# PlatingBoard.net
KiCad netlist of a schematic drawn in EAGLE
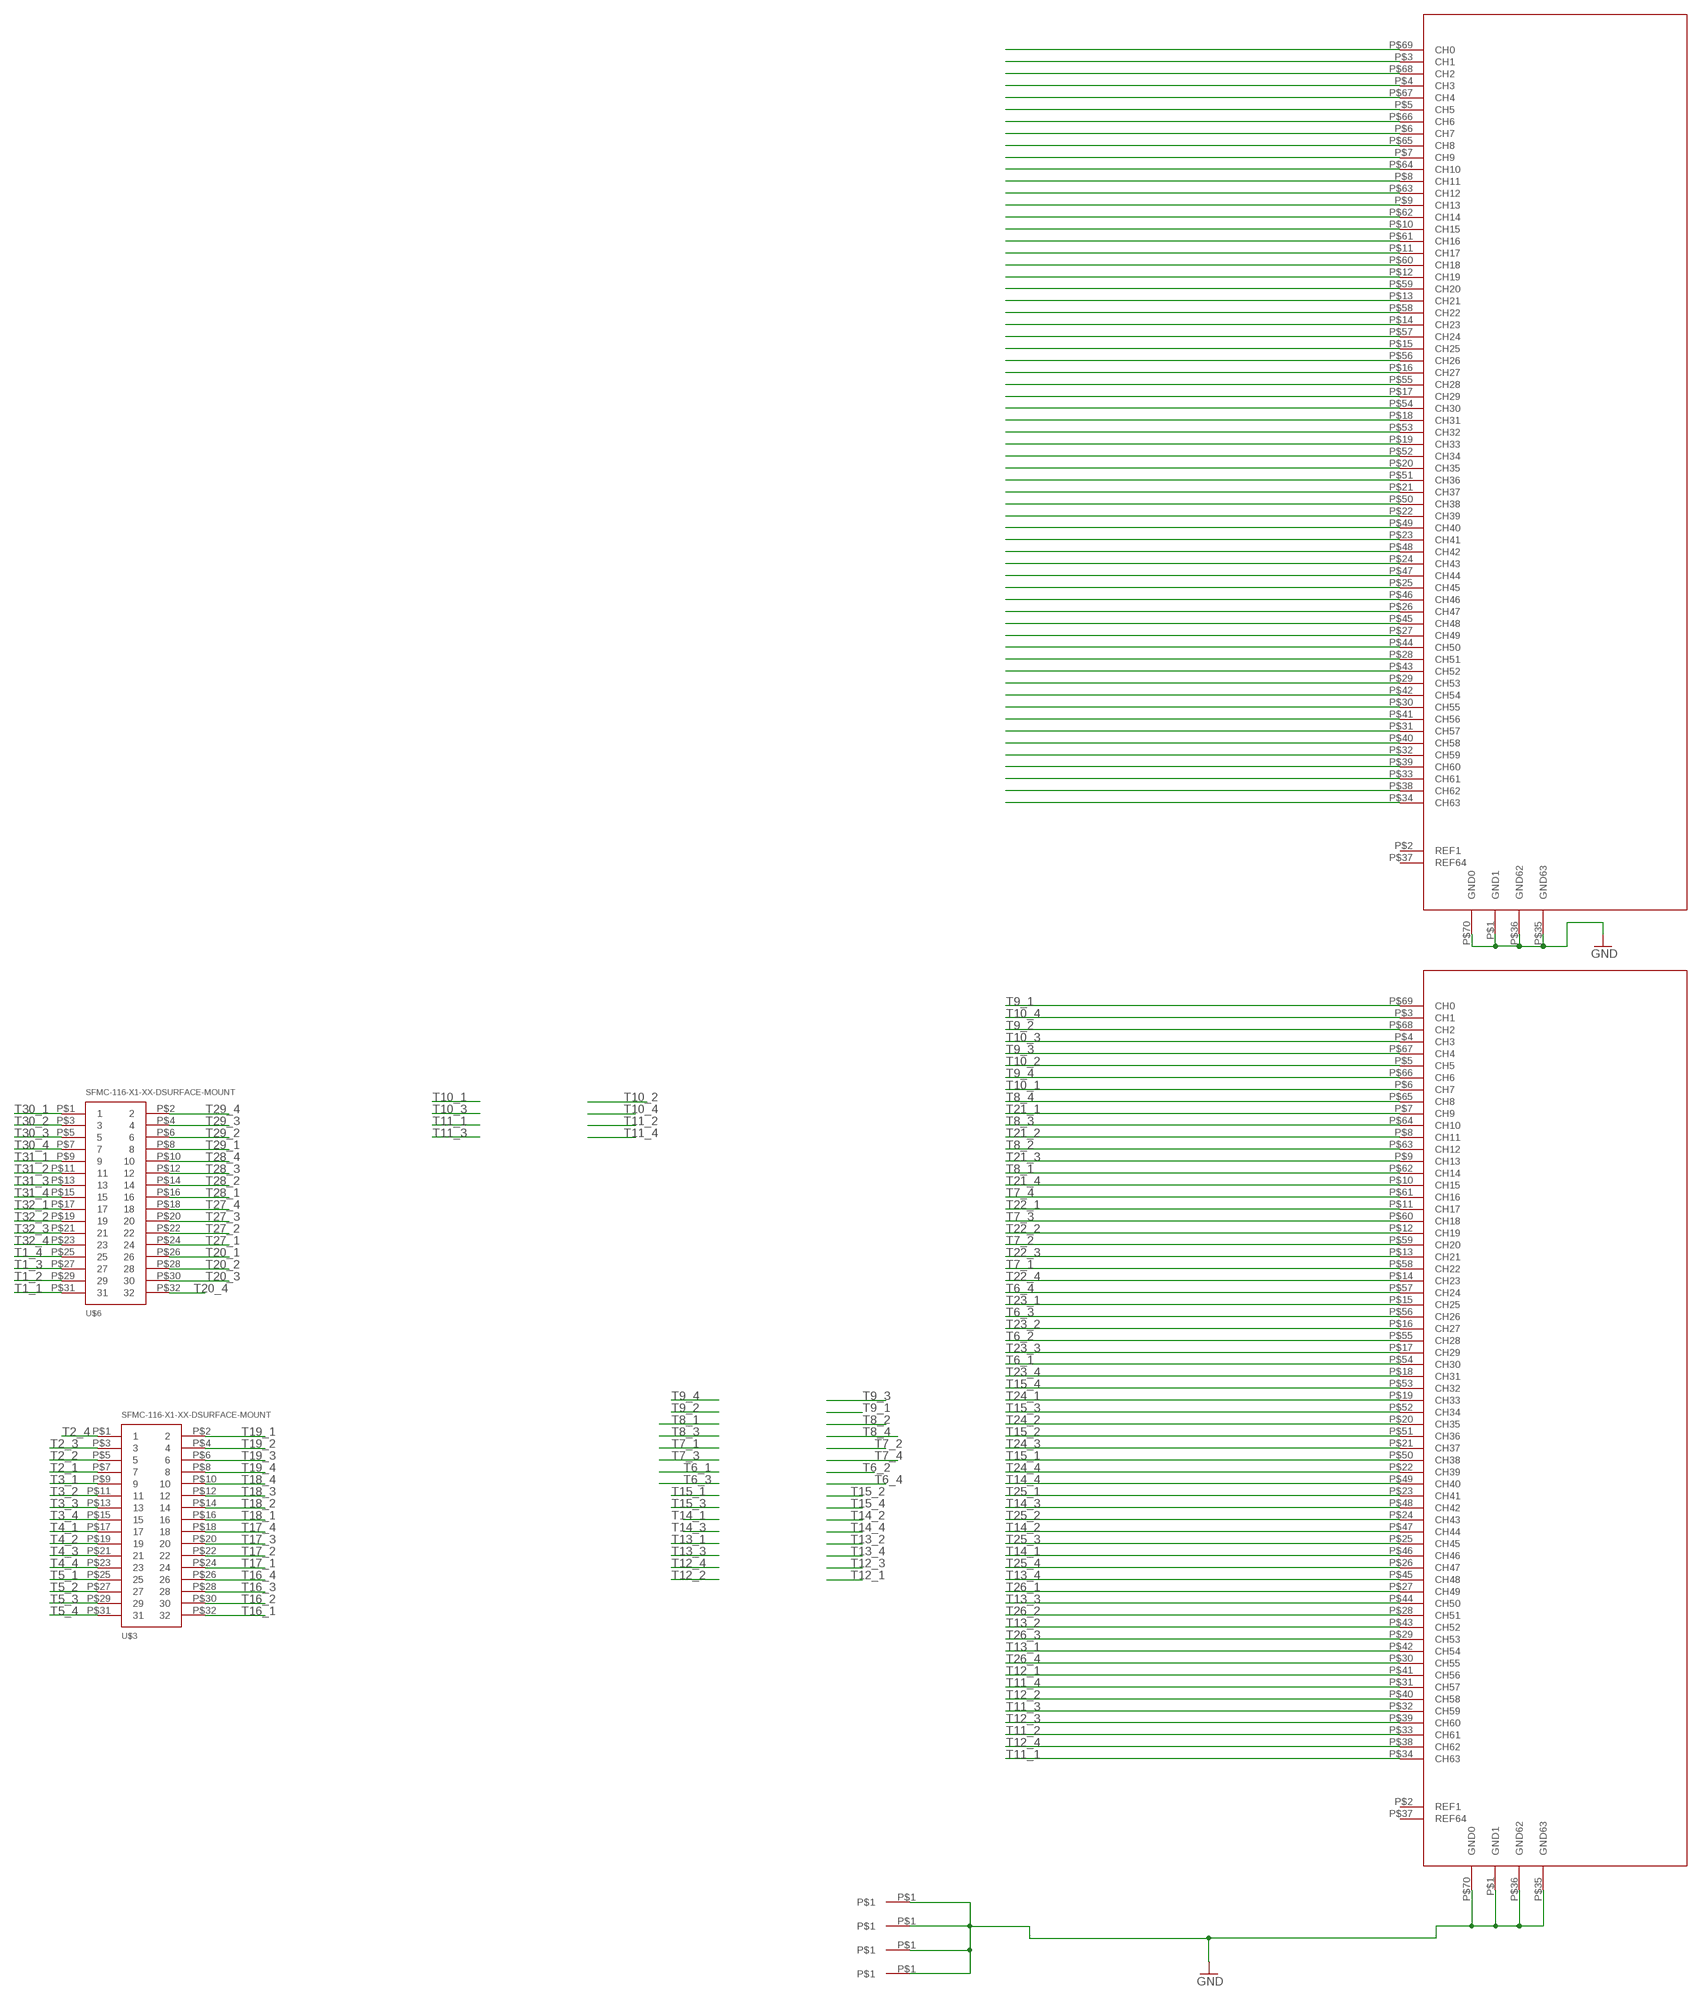
[diagram p0: schematic, sheet 1]

(export (version "E")
  (design (tool "Eeschema 10.0.6"))
  (components
    (comp (ref "U$1")
      (value "TARRAYSHUTTLEHOLE")
      (footprint "eagle-import:TARRAYSHUTTLEHOLE")
      (libsource (lib "eagle-import") (part "TARRAYSHUTTLEHOLE"))
    )
    (comp (ref "U$2")
      (value "TARRAYSHUTTLEHOLE")
      (footprint "eagle-import:TARRAYSHUTTLEHOLE")
      (libsource (lib "eagle-import") (part "TARRAYSHUTTLEHOLE"))
    )
    (comp (ref "U$3")
      (value "SFMC-116-X1-XX-DSURFACE-MOUNT")
      (footprint "eagle-import:SFMC-116-X2-XX-D")
      (libsource (lib "eagle-import") (part "SFMC-116-X1-XX-DSURFACE-MOUNT"))
    )
    (comp (ref "U$4")
      (value "TARRAYSHUTTLEHOLE")
      (footprint "eagle-import:TARRAYSHUTTLEHOLE")
      (libsource (lib "eagle-import") (part "TARRAYSHUTTLEHOLE"))
    )
    (comp (ref "U$5")
      (value "TARRAYSHUTTLEHOLE")
      (footprint "eagle-import:TARRAYSHUTTLEHOLE")
      (libsource (lib "eagle-import") (part "TARRAYSHUTTLEHOLE"))
    )
    (comp (ref "U$6")
      (value "SFMC-116-X1-XX-DSURFACE-MOUNT")
      (footprint "eagle-import:SFMC-116-X2-XX-D")
      (libsource (lib "eagle-import") (part "SFMC-116-X1-XX-DSURFACE-MOUNT"))
    )
    (comp (ref "U$11")
      (value "HIROSE-70PIN-RECEPTACLE")
      (footprint "eagle-import:DF40HC-70DS-0.4V")
      (libsource (lib "eagle-import") (part "HIROSE-70PIN-RECEPTACLE"))
    )
    (comp (ref "U$13")
      (value "HIROSE-70PIN-RECEPTACLE")
      (footprint "eagle-import:DF40HC-70DS-0.4V")
      (libsource (lib "eagle-import") (part "HIROSE-70PIN-RECEPTACLE"))
    )
  )
  (nets
    (net (code "1") (name "/T1_1") (class "Default")
      (node (ref "U$11") (pin "P$34") (pinfunction "CH63_P$34") (pintype "input"))
      (node (ref "U$6") (pin "P$31") (pinfunction "31_P$31") (pintype "bidirectional"))
    )
    (net (code "2") (name "/T1_2") (class "Default")
      (node (ref "U$11") (pin "P$33") (pinfunction "CH61_P$33") (pintype "input"))
      (node (ref "U$6") (pin "P$29") (pinfunction "29_P$29") (pintype "bidirectional"))
    )
    (net (code "3") (name "/T1_3") (class "Default")
      (node (ref "U$11") (pin "P$32") (pinfunction "CH59_P$32") (pintype "input"))
      (node (ref "U$6") (pin "P$27") (pinfunction "27_P$27") (pintype "bidirectional"))
    )
    (net (code "4") (name "/T1_4") (class "Default")
      (node (ref "U$11") (pin "P$31") (pinfunction "CH57_P$31") (pintype "input"))
      (node (ref "U$6") (pin "P$25") (pinfunction "25_P$25") (pintype "bidirectional"))
    )
    (net (code "5") (name "/T2_1") (class "Default")
      (node (ref "U$11") (pin "P$41") (pinfunction "CH56_P$41") (pintype "input"))
      (node (ref "U$3") (pin "P$7") (pinfunction "7_P$7") (pintype "bidirectional"))
    )
    (net (code "6") (name "/T2_2") (class "Default")
      (node (ref "U$11") (pin "P$40") (pinfunction "CH58_P$40") (pintype "input"))
      (node (ref "U$3") (pin "P$5") (pinfunction "5_P$5") (pintype "bidirectional"))
    )
    (net (code "7") (name "/T2_3") (class "Default")
      (node (ref "U$11") (pin "P$39") (pinfunction "CH60_P$39") (pintype "input"))
      (node (ref "U$3") (pin "P$3") (pinfunction "3_P$3") (pintype "bidirectional"))
    )
    (net (code "8") (name "/T2_4") (class "Default")
      (node (ref "U$11") (pin "P$38") (pinfunction "CH62_P$38") (pintype "input"))
      (node (ref "U$3") (pin "P$1") (pinfunction "1_P$1") (pintype "bidirectional"))
    )
    (net (code "9") (name "/T3_1") (class "Default")
      (node (ref "U$11") (pin "P$42") (pinfunction "CH54_P$42") (pintype "input"))
      (node (ref "U$3") (pin "P$9") (pinfunction "9_P$9") (pintype "bidirectional"))
    )
    (net (code "10") (name "/T3_2") (class "Default")
      (node (ref "U$11") (pin "P$43") (pinfunction "CH52_P$43") (pintype "input"))
      (node (ref "U$3") (pin "P$11") (pinfunction "11_P$11") (pintype "bidirectional"))
    )
    (net (code "11") (name "/T3_3") (class "Default")
      (node (ref "U$11") (pin "P$44") (pinfunction "CH50_P$44") (pintype "input"))
      (node (ref "U$3") (pin "P$13") (pinfunction "13_P$13") (pintype "bidirectional"))
    )
    (net (code "12") (name "/T3_4") (class "Default")
      (node (ref "U$11") (pin "P$45") (pinfunction "CH48_P$45") (pintype "input"))
      (node (ref "U$3") (pin "P$15") (pinfunction "15_P$15") (pintype "bidirectional"))
    )
    (net (code "13") (name "/T4_1") (class "Default")
      (node (ref "U$11") (pin "P$46") (pinfunction "CH46_P$46") (pintype "input"))
      (node (ref "U$3") (pin "P$17") (pinfunction "17_P$17") (pintype "bidirectional"))
    )
    (net (code "14") (name "/T4_2") (class "Default")
      (node (ref "U$11") (pin "P$47") (pinfunction "CH44_P$47") (pintype "input"))
      (node (ref "U$3") (pin "P$19") (pinfunction "19_P$19") (pintype "bidirectional"))
    )
    (net (code "15") (name "/T4_3") (class "Default")
      (node (ref "U$11") (pin "P$48") (pinfunction "CH42_P$48") (pintype "input"))
      (node (ref "U$3") (pin "P$21") (pinfunction "21_P$21") (pintype "bidirectional"))
    )
    (net (code "16") (name "/T4_4") (class "Default")
      (node (ref "U$11") (pin "P$49") (pinfunction "CH40_P$49") (pintype "input"))
      (node (ref "U$3") (pin "P$23") (pinfunction "23_P$23") (pintype "bidirectional"))
    )
    (net (code "17") (name "/T5_1") (class "Default")
      (node (ref "U$11") (pin "P$50") (pinfunction "CH38_P$50") (pintype "input"))
      (node (ref "U$3") (pin "P$25") (pinfunction "25_P$25") (pintype "bidirectional"))
    )
    (net (code "18") (name "/T5_2") (class "Default")
      (node (ref "U$11") (pin "P$51") (pinfunction "CH36_P$51") (pintype "input"))
      (node (ref "U$3") (pin "P$27") (pinfunction "27_P$27") (pintype "bidirectional"))
    )
    (net (code "19") (name "/T5_3") (class "Default")
      (node (ref "U$11") (pin "P$52") (pinfunction "CH34_P$52") (pintype "input"))
      (node (ref "U$3") (pin "P$29") (pinfunction "29_P$29") (pintype "bidirectional"))
    )
    (net (code "20") (name "/T5_4") (class "Default")
      (node (ref "U$11") (pin "P$53") (pinfunction "CH32_P$53") (pintype "input"))
      (node (ref "U$3") (pin "P$31") (pinfunction "31_P$31") (pintype "bidirectional"))
    )
    (net (code "21") (name "/T6_1") (class "Default")
      (node (ref "U$13") (pin "P$54") (pinfunction "CH30_P$54") (pintype "input"))
    )
    (net (code "22") (name "/T6_2") (class "Default")
      (node (ref "U$13") (pin "P$55") (pinfunction "CH28_P$55") (pintype "input"))
    )
    (net (code "23") (name "/T6_3") (class "Default")
      (node (ref "U$13") (pin "P$56") (pinfunction "CH26_P$56") (pintype "input"))
    )
    (net (code "24") (name "/T6_4") (class "Default")
      (node (ref "U$13") (pin "P$57") (pinfunction "CH24_P$57") (pintype "input"))
    )
    (net (code "25") (name "/T7_1") (class "Default")
      (node (ref "U$13") (pin "P$58") (pinfunction "CH22_P$58") (pintype "input"))
    )
    (net (code "26") (name "/T7_2") (class "Default")
      (node (ref "U$13") (pin "P$59") (pinfunction "CH20_P$59") (pintype "input"))
    )
    (net (code "27") (name "/T7_3") (class "Default")
      (node (ref "U$13") (pin "P$60") (pinfunction "CH18_P$60") (pintype "input"))
    )
    (net (code "28") (name "/T7_4") (class "Default")
      (node (ref "U$13") (pin "P$61") (pinfunction "CH16_P$61") (pintype "input"))
    )
    (net (code "29") (name "/T8_1") (class "Default")
      (node (ref "U$13") (pin "P$62") (pinfunction "CH14_P$62") (pintype "input"))
    )
    (net (code "30") (name "/T8_2") (class "Default")
      (node (ref "U$13") (pin "P$63") (pinfunction "CH12_P$63") (pintype "input"))
    )
    (net (code "31") (name "/T8_3") (class "Default")
      (node (ref "U$13") (pin "P$64") (pinfunction "CH10_P$64") (pintype "input"))
    )
    (net (code "32") (name "/T8_4") (class "Default")
      (node (ref "U$13") (pin "P$65") (pinfunction "CH8_P$65") (pintype "input"))
    )
    (net (code "33") (name "/T9_1") (class "Default")
      (node (ref "U$13") (pin "P$69") (pinfunction "CH0_P$69") (pintype "input"))
    )
    (net (code "34") (name "/T9_2") (class "Default")
      (node (ref "U$13") (pin "P$68") (pinfunction "CH2_P$68") (pintype "input"))
    )
    (net (code "35") (name "/T9_3") (class "Default")
      (node (ref "U$13") (pin "P$67") (pinfunction "CH4_P$67") (pintype "input"))
    )
    (net (code "36") (name "/T9_4") (class "Default")
      (node (ref "U$13") (pin "P$66") (pinfunction "CH6_P$66") (pintype "input"))
    )
    (net (code "37") (name "/T10_1") (class "Default")
      (node (ref "U$13") (pin "P$6") (pinfunction "CH7_P$6") (pintype "input"))
    )
    (net (code "38") (name "/T10_2") (class "Default")
      (node (ref "U$13") (pin "P$5") (pinfunction "CH5_P$5") (pintype "input"))
    )
    (net (code "39") (name "/T10_3") (class "Default")
      (node (ref "U$13") (pin "P$4") (pinfunction "CH3_P$4") (pintype "input"))
    )
    (net (code "40") (name "/T10_4") (class "Default")
      (node (ref "U$13") (pin "P$3") (pinfunction "CH1_P$3") (pintype "input"))
    )
    (net (code "41") (name "/T11_1") (class "Default")
      (node (ref "U$13") (pin "P$34") (pinfunction "CH63_P$34") (pintype "input"))
    )
    (net (code "42") (name "/T11_2") (class "Default")
      (node (ref "U$13") (pin "P$33") (pinfunction "CH61_P$33") (pintype "input"))
    )
    (net (code "43") (name "/T11_3") (class "Default")
      (node (ref "U$13") (pin "P$32") (pinfunction "CH59_P$32") (pintype "input"))
    )
    (net (code "44") (name "/T11_4") (class "Default")
      (node (ref "U$13") (pin "P$31") (pinfunction "CH57_P$31") (pintype "input"))
    )
    (net (code "45") (name "/T12_1") (class "Default")
      (node (ref "U$13") (pin "P$41") (pinfunction "CH56_P$41") (pintype "input"))
    )
    (net (code "46") (name "/T12_2") (class "Default")
      (node (ref "U$13") (pin "P$40") (pinfunction "CH58_P$40") (pintype "input"))
    )
    (net (code "47") (name "/T12_3") (class "Default")
      (node (ref "U$13") (pin "P$39") (pinfunction "CH60_P$39") (pintype "input"))
    )
    (net (code "48") (name "/T12_4") (class "Default")
      (node (ref "U$13") (pin "P$38") (pinfunction "CH62_P$38") (pintype "input"))
    )
    (net (code "49") (name "/T13_1") (class "Default")
      (node (ref "U$13") (pin "P$42") (pinfunction "CH54_P$42") (pintype "input"))
    )
    (net (code "50") (name "/T13_2") (class "Default")
      (node (ref "U$13") (pin "P$43") (pinfunction "CH52_P$43") (pintype "input"))
    )
    (net (code "51") (name "/T13_3") (class "Default")
      (node (ref "U$13") (pin "P$44") (pinfunction "CH50_P$44") (pintype "input"))
    )
    (net (code "52") (name "/T13_4") (class "Default")
      (node (ref "U$13") (pin "P$45") (pinfunction "CH48_P$45") (pintype "input"))
    )
    (net (code "53") (name "/T14_1") (class "Default")
      (node (ref "U$13") (pin "P$46") (pinfunction "CH46_P$46") (pintype "input"))
    )
    (net (code "54") (name "/T14_2") (class "Default")
      (node (ref "U$13") (pin "P$47") (pinfunction "CH44_P$47") (pintype "input"))
    )
    (net (code "55") (name "/T14_3") (class "Default")
      (node (ref "U$13") (pin "P$48") (pinfunction "CH42_P$48") (pintype "input"))
    )
    (net (code "56") (name "/T14_4") (class "Default")
      (node (ref "U$13") (pin "P$49") (pinfunction "CH40_P$49") (pintype "input"))
    )
    (net (code "57") (name "/T15_1") (class "Default")
      (node (ref "U$13") (pin "P$50") (pinfunction "CH38_P$50") (pintype "input"))
    )
    (net (code "58") (name "/T15_2") (class "Default")
      (node (ref "U$13") (pin "P$51") (pinfunction "CH36_P$51") (pintype "input"))
    )
    (net (code "59") (name "/T15_3") (class "Default")
      (node (ref "U$13") (pin "P$52") (pinfunction "CH34_P$52") (pintype "input"))
    )
    (net (code "60") (name "/T15_4") (class "Default")
      (node (ref "U$13") (pin "P$53") (pinfunction "CH32_P$53") (pintype "input"))
    )
    (net (code "61") (name "/T16_1") (class "Default")
      (node (ref "U$11") (pin "P$54") (pinfunction "CH30_P$54") (pintype "input"))
      (node (ref "U$3") (pin "P$32") (pinfunction "32_P$32") (pintype "bidirectional"))
    )
    (net (code "62") (name "/T16_2") (class "Default")
      (node (ref "U$11") (pin "P$55") (pinfunction "CH28_P$55") (pintype "input"))
      (node (ref "U$3") (pin "P$30") (pinfunction "30_P$30") (pintype "bidirectional"))
    )
    (net (code "63") (name "/T16_3") (class "Default")
      (node (ref "U$11") (pin "P$56") (pinfunction "CH26_P$56") (pintype "input"))
      (node (ref "U$3") (pin "P$28") (pinfunction "28_P$28") (pintype "bidirectional"))
    )
    (net (code "64") (name "/T16_4") (class "Default")
      (node (ref "U$11") (pin "P$57") (pinfunction "CH24_P$57") (pintype "input"))
      (node (ref "U$3") (pin "P$26") (pinfunction "26_P$26") (pintype "bidirectional"))
    )
    (net (code "65") (name "/T17_1") (class "Default")
      (node (ref "U$11") (pin "P$58") (pinfunction "CH22_P$58") (pintype "input"))
      (node (ref "U$3") (pin "P$24") (pinfunction "24_P$24") (pintype "bidirectional"))
    )
    (net (code "66") (name "/T17_2") (class "Default")
      (node (ref "U$11") (pin "P$59") (pinfunction "CH20_P$59") (pintype "input"))
      (node (ref "U$3") (pin "P$22") (pinfunction "22_P$22") (pintype "bidirectional"))
    )
    (net (code "67") (name "/T17_3") (class "Default")
      (node (ref "U$11") (pin "P$60") (pinfunction "CH18_P$60") (pintype "input"))
      (node (ref "U$3") (pin "P$20") (pinfunction "20_P$20") (pintype "bidirectional"))
    )
    (net (code "68") (name "/T17_4") (class "Default")
      (node (ref "U$11") (pin "P$61") (pinfunction "CH16_P$61") (pintype "input"))
      (node (ref "U$3") (pin "P$18") (pinfunction "18_P$18") (pintype "bidirectional"))
    )
    (net (code "69") (name "/T18_1") (class "Default")
      (node (ref "U$11") (pin "P$62") (pinfunction "CH14_P$62") (pintype "input"))
      (node (ref "U$3") (pin "P$16") (pinfunction "16_P$16") (pintype "bidirectional"))
    )
    (net (code "70") (name "/T18_2") (class "Default")
      (node (ref "U$11") (pin "P$63") (pinfunction "CH12_P$63") (pintype "input"))
      (node (ref "U$3") (pin "P$14") (pinfunction "14_P$14") (pintype "bidirectional"))
    )
    (net (code "71") (name "/T18_3") (class "Default")
      (node (ref "U$11") (pin "P$64") (pinfunction "CH10_P$64") (pintype "input"))
      (node (ref "U$3") (pin "P$12") (pinfunction "12_P$12") (pintype "bidirectional"))
    )
    (net (code "72") (name "/T18_4") (class "Default")
      (node (ref "U$11") (pin "P$65") (pinfunction "CH8_P$65") (pintype "input"))
      (node (ref "U$3") (pin "P$10") (pinfunction "10_P$10") (pintype "bidirectional"))
    )
    (net (code "73") (name "/T19_1") (class "Default")
      (node (ref "U$11") (pin "P$69") (pinfunction "CH0_P$69") (pintype "input"))
      (node (ref "U$3") (pin "P$2") (pinfunction "2_P$2") (pintype "bidirectional"))
    )
    (net (code "74") (name "/T19_2") (class "Default")
      (node (ref "U$11") (pin "P$68") (pinfunction "CH2_P$68") (pintype "input"))
      (node (ref "U$3") (pin "P$4") (pinfunction "4_P$4") (pintype "bidirectional"))
    )
    (net (code "75") (name "/T19_3") (class "Default")
      (node (ref "U$11") (pin "P$67") (pinfunction "CH4_P$67") (pintype "input"))
      (node (ref "U$3") (pin "P$6") (pinfunction "6_P$6") (pintype "bidirectional"))
    )
    (net (code "76") (name "/T19_4") (class "Default")
      (node (ref "U$11") (pin "P$66") (pinfunction "CH6_P$66") (pintype "input"))
      (node (ref "U$3") (pin "P$8") (pinfunction "8_P$8") (pintype "bidirectional"))
    )
    (net (code "77") (name "/T20_1") (class "Default")
      (node (ref "U$11") (pin "P$6") (pinfunction "CH7_P$6") (pintype "input"))
      (node (ref "U$6") (pin "P$26") (pinfunction "26_P$26") (pintype "bidirectional"))
    )
    (net (code "78") (name "/T20_2") (class "Default")
      (node (ref "U$11") (pin "P$5") (pinfunction "CH5_P$5") (pintype "input"))
      (node (ref "U$6") (pin "P$28") (pinfunction "28_P$28") (pintype "bidirectional"))
    )
    (net (code "79") (name "/T20_3") (class "Default")
      (node (ref "U$11") (pin "P$4") (pinfunction "CH3_P$4") (pintype "input"))
      (node (ref "U$6") (pin "P$30") (pinfunction "30_P$30") (pintype "bidirectional"))
    )
    (net (code "80") (name "/T20_4") (class "Default")
      (node (ref "U$11") (pin "P$3") (pinfunction "CH1_P$3") (pintype "input"))
      (node (ref "U$6") (pin "P$32") (pinfunction "32_P$32") (pintype "bidirectional"))
    )
    (net (code "81") (name "/T21_1") (class "Default")
      (node (ref "U$13") (pin "P$7") (pinfunction "CH9_P$7") (pintype "input"))
    )
    (net (code "82") (name "/T21_2") (class "Default")
      (node (ref "U$13") (pin "P$8") (pinfunction "CH11_P$8") (pintype "input"))
    )
    (net (code "83") (name "/T21_3") (class "Default")
      (node (ref "U$13") (pin "P$9") (pinfunction "CH13_P$9") (pintype "input"))
    )
    (net (code "84") (name "/T21_4") (class "Default")
      (node (ref "U$13") (pin "P$10") (pinfunction "CH15_P$10") (pintype "input"))
    )
    (net (code "85") (name "/T22_1") (class "Default")
      (node (ref "U$13") (pin "P$11") (pinfunction "CH17_P$11") (pintype "input"))
    )
    (net (code "86") (name "/T22_2") (class "Default")
      (node (ref "U$13") (pin "P$12") (pinfunction "CH19_P$12") (pintype "input"))
    )
    (net (code "87") (name "/T22_3") (class "Default")
      (node (ref "U$13") (pin "P$13") (pinfunction "CH21_P$13") (pintype "input"))
    )
    (net (code "88") (name "/T22_4") (class "Default")
      (node (ref "U$13") (pin "P$14") (pinfunction "CH23_P$14") (pintype "input"))
    )
    (net (code "89") (name "/T23_1") (class "Default")
      (node (ref "U$13") (pin "P$15") (pinfunction "CH25_P$15") (pintype "input"))
    )
    (net (code "90") (name "/T23_2") (class "Default")
      (node (ref "U$13") (pin "P$16") (pinfunction "CH27_P$16") (pintype "input"))
    )
    (net (code "91") (name "/T23_3") (class "Default")
      (node (ref "U$13") (pin "P$17") (pinfunction "CH29_P$17") (pintype "input"))
    )
    (net (code "92") (name "/T23_4") (class "Default")
      (node (ref "U$13") (pin "P$18") (pinfunction "CH31_P$18") (pintype "input"))
    )
    (net (code "93") (name "/T24_1") (class "Default")
      (node (ref "U$13") (pin "P$19") (pinfunction "CH33_P$19") (pintype "input"))
    )
    (net (code "94") (name "/T24_2") (class "Default")
      (node (ref "U$13") (pin "P$20") (pinfunction "CH35_P$20") (pintype "input"))
    )
    (net (code "95") (name "/T24_3") (class "Default")
      (node (ref "U$13") (pin "P$21") (pinfunction "CH37_P$21") (pintype "input"))
    )
    (net (code "96") (name "/T24_4") (class "Default")
      (node (ref "U$13") (pin "P$22") (pinfunction "CH39_P$22") (pintype "input"))
    )
    (net (code "97") (name "/T25_1") (class "Default")
      (node (ref "U$13") (pin "P$23") (pinfunction "CH41_P$23") (pintype "input"))
    )
    (net (code "98") (name "/T25_2") (class "Default")
      (node (ref "U$13") (pin "P$24") (pinfunction "CH43_P$24") (pintype "input"))
    )
    (net (code "99") (name "/T25_3") (class "Default")
      (node (ref "U$13") (pin "P$25") (pinfunction "CH45_P$25") (pintype "input"))
    )
    (net (code "100") (name "/T25_4") (class "Default")
      (node (ref "U$13") (pin "P$26") (pinfunction "CH47_P$26") (pintype "input"))
    )
    (net (code "101") (name "/T26_1") (class "Default")
      (node (ref "U$13") (pin "P$27") (pinfunction "CH49_P$27") (pintype "input"))
    )
    (net (code "102") (name "/T26_2") (class "Default")
      (node (ref "U$13") (pin "P$28") (pinfunction "CH51_P$28") (pintype "input"))
    )
    (net (code "103") (name "/T26_3") (class "Default")
      (node (ref "U$13") (pin "P$29") (pinfunction "CH53_P$29") (pintype "input"))
    )
    (net (code "104") (name "/T26_4") (class "Default")
      (node (ref "U$13") (pin "P$30") (pinfunction "CH55_P$30") (pintype "input"))
    )
    (net (code "105") (name "/T27_1") (class "Default")
      (node (ref "U$11") (pin "P$7") (pinfunction "CH9_P$7") (pintype "input"))
      (node (ref "U$6") (pin "P$24") (pinfunction "24_P$24") (pintype "bidirectional"))
    )
    (net (code "106") (name "/T27_2") (class "Default")
      (node (ref "U$11") (pin "P$8") (pinfunction "CH11_P$8") (pintype "input"))
      (node (ref "U$6") (pin "P$22") (pinfunction "22_P$22") (pintype "bidirectional"))
    )
    (net (code "107") (name "/T27_3") (class "Default")
      (node (ref "U$11") (pin "P$9") (pinfunction "CH13_P$9") (pintype "input"))
      (node (ref "U$6") (pin "P$20") (pinfunction "20_P$20") (pintype "bidirectional"))
    )
    (net (code "108") (name "/T27_4") (class "Default")
      (node (ref "U$11") (pin "P$10") (pinfunction "CH15_P$10") (pintype "input"))
      (node (ref "U$6") (pin "P$18") (pinfunction "18_P$18") (pintype "bidirectional"))
    )
    (net (code "109") (name "/T28_1") (class "Default")
      (node (ref "U$11") (pin "P$11") (pinfunction "CH17_P$11") (pintype "input"))
      (node (ref "U$6") (pin "P$16") (pinfunction "16_P$16") (pintype "bidirectional"))
    )
    (net (code "110") (name "/T28_2") (class "Default")
      (node (ref "U$11") (pin "P$12") (pinfunction "CH19_P$12") (pintype "input"))
      (node (ref "U$6") (pin "P$14") (pinfunction "14_P$14") (pintype "bidirectional"))
    )
    (net (code "111") (name "/T28_3") (class "Default")
      (node (ref "U$11") (pin "P$13") (pinfunction "CH21_P$13") (pintype "input"))
      (node (ref "U$6") (pin "P$12") (pinfunction "12_P$12") (pintype "bidirectional"))
    )
    (net (code "112") (name "/T28_4") (class "Default")
      (node (ref "U$11") (pin "P$14") (pinfunction "CH23_P$14") (pintype "input"))
      (node (ref "U$6") (pin "P$10") (pinfunction "10_P$10") (pintype "bidirectional"))
    )
    (net (code "113") (name "/T29_1") (class "Default")
      (node (ref "U$11") (pin "P$15") (pinfunction "CH25_P$15") (pintype "input"))
      (node (ref "U$6") (pin "P$8") (pinfunction "8_P$8") (pintype "bidirectional"))
    )
    (net (code "114") (name "/T29_2") (class "Default")
      (node (ref "U$11") (pin "P$16") (pinfunction "CH27_P$16") (pintype "input"))
      (node (ref "U$6") (pin "P$6") (pinfunction "6_P$6") (pintype "bidirectional"))
    )
    (net (code "115") (name "/T29_3") (class "Default")
      (node (ref "U$11") (pin "P$17") (pinfunction "CH29_P$17") (pintype "input"))
      (node (ref "U$6") (pin "P$4") (pinfunction "4_P$4") (pintype "bidirectional"))
    )
    (net (code "116") (name "/T29_4") (class "Default")
      (node (ref "U$11") (pin "P$18") (pinfunction "CH31_P$18") (pintype "input"))
      (node (ref "U$6") (pin "P$2") (pinfunction "2_P$2") (pintype "bidirectional"))
    )
    (net (code "117") (name "/T30_1") (class "Default")
      (node (ref "U$11") (pin "P$19") (pinfunction "CH33_P$19") (pintype "input"))
      (node (ref "U$6") (pin "P$1") (pinfunction "1_P$1") (pintype "bidirectional"))
    )
    (net (code "118") (name "/T30_2") (class "Default")
      (node (ref "U$11") (pin "P$20") (pinfunction "CH35_P$20") (pintype "input"))
      (node (ref "U$6") (pin "P$3") (pinfunction "3_P$3") (pintype "bidirectional"))
    )
    (net (code "119") (name "/T30_3") (class "Default")
      (node (ref "U$11") (pin "P$21") (pinfunction "CH37_P$21") (pintype "input"))
      (node (ref "U$6") (pin "P$5") (pinfunction "5_P$5") (pintype "bidirectional"))
    )
    (net (code "120") (name "/T30_4") (class "Default")
      (node (ref "U$11") (pin "P$22") (pinfunction "CH39_P$22") (pintype "input"))
      (node (ref "U$6") (pin "P$7") (pinfunction "7_P$7") (pintype "bidirectional"))
    )
    (net (code "121") (name "/T31_1") (class "Default")
      (node (ref "U$11") (pin "P$23") (pinfunction "CH41_P$23") (pintype "input"))
      (node (ref "U$6") (pin "P$9") (pinfunction "9_P$9") (pintype "bidirectional"))
    )
    (net (code "122") (name "/T31_2") (class "Default")
      (node (ref "U$11") (pin "P$24") (pinfunction "CH43_P$24") (pintype "input"))
      (node (ref "U$6") (pin "P$11") (pinfunction "11_P$11") (pintype "bidirectional"))
    )
    (net (code "123") (name "/T31_3") (class "Default")
      (node (ref "U$11") (pin "P$25") (pinfunction "CH45_P$25") (pintype "input"))
      (node (ref "U$6") (pin "P$13") (pinfunction "13_P$13") (pintype "bidirectional"))
    )
    (net (code "124") (name "/T31_4") (class "Default")
      (node (ref "U$11") (pin "P$26") (pinfunction "CH47_P$26") (pintype "input"))
      (node (ref "U$6") (pin "P$15") (pinfunction "15_P$15") (pintype "bidirectional"))
    )
    (net (code "125") (name "/T32_1") (class "Default")
      (node (ref "U$11") (pin "P$27") (pinfunction "CH49_P$27") (pintype "input"))
      (node (ref "U$6") (pin "P$17") (pinfunction "17_P$17") (pintype "bidirectional"))
    )
    (net (code "126") (name "/T32_2") (class "Default")
      (node (ref "U$11") (pin "P$28") (pinfunction "CH51_P$28") (pintype "input"))
      (node (ref "U$6") (pin "P$19") (pinfunction "19_P$19") (pintype "bidirectional"))
    )
    (net (code "127") (name "/T32_3") (class "Default")
      (node (ref "U$11") (pin "P$29") (pinfunction "CH53_P$29") (pintype "input"))
      (node (ref "U$6") (pin "P$21") (pinfunction "21_P$21") (pintype "bidirectional"))
    )
    (net (code "128") (name "/T32_4") (class "Default")
      (node (ref "U$11") (pin "P$30") (pinfunction "CH55_P$30") (pintype "input"))
      (node (ref "U$6") (pin "P$23") (pinfunction "23_P$23") (pintype "bidirectional"))
    )
    (net (code "129") (name "GND") (class "Default")
      (node (ref "U$1") (pin "P$1") (pinfunction "P$1_P$1") (pintype "bidirectional"))
      (node (ref "U$11") (pin "P$1") (pinfunction "GND1_P$1") (pintype "power_in"))
      (node (ref "U$11") (pin "P$35") (pinfunction "GND63_P$35") (pintype "power_in"))
      (node (ref "U$11") (pin "P$36") (pinfunction "GND62_P$36") (pintype "power_in"))
      (node (ref "U$11") (pin "P$70") (pinfunction "GND0_P$70") (pintype "power_in"))
      (node (ref "U$13") (pin "P$1") (pinfunction "GND1_P$1") (pintype "power_in"))
      (node (ref "U$13") (pin "P$35") (pinfunction "GND63_P$35") (pintype "power_in"))
      (node (ref "U$13") (pin "P$36") (pinfunction "GND62_P$36") (pintype "power_in"))
      (node (ref "U$13") (pin "P$70") (pinfunction "GND0_P$70") (pintype "power_in"))
      (node (ref "U$2") (pin "P$1") (pinfunction "P$1_P$1") (pintype "bidirectional"))
      (node (ref "U$4") (pin "P$1") (pinfunction "P$1_P$1") (pintype "bidirectional"))
      (node (ref "U$5") (pin "P$1") (pinfunction "P$1_P$1") (pintype "bidirectional"))
    )
    (net (code "130") (name "unconnected-(U$11-REF1-PadP$2)") (class "Default")
      (node (ref "U$11") (pin "P$2") (pinfunction "REF1_P$2") (pintype "input"))
    )
    (net (code "131") (name "unconnected-(U$11-REF64-PadP$37)") (class "Default")
      (node (ref "U$11") (pin "P$37") (pinfunction "REF64_P$37") (pintype "input"))
    )
    (net (code "132") (name "unconnected-(U$13-REF1-PadP$2)") (class "Default")
      (node (ref "U$13") (pin "P$2") (pinfunction "REF1_P$2") (pintype "input"))
    )
    (net (code "133") (name "unconnected-(U$13-REF64-PadP$37)") (class "Default")
      (node (ref "U$13") (pin "P$37") (pinfunction "REF64_P$37") (pintype "input"))
    )
  )
)
